# Digital_Clock.net
KiCad netlist of a schematic drawn in Altium Designer
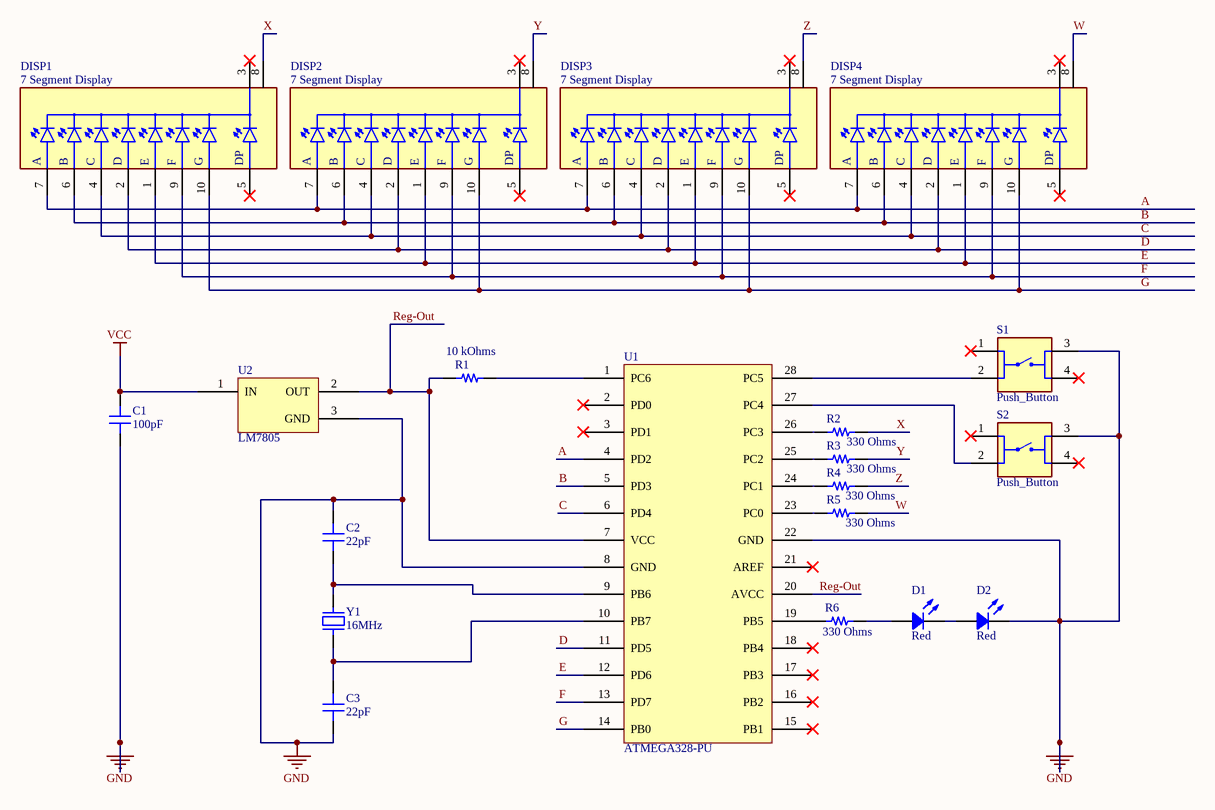
[diagram p0: Digital_Clock.SchDoc]

(export (version "E")
  (design (tool "Eeschema 10.0.6"))
  (components
    (comp (ref "C1")
      (value "100pF")
      (footprint "CAP 0805_2012")
      (description "CAP CER 100PF 25V NP0 0805")
      (fields
        (field (name "PART NUMBER") "08053A101J4T2A")
        (field (name "CAPACITANCE") "100pF")
        (field (name "MANUFACTURER") "AVX Corporation")
      )
      (libsource (lib "Celestial Altium Library - altium_library") (part "Capacitor"))
    )
    (comp (ref "C2")
      (value "22pF")
      (footprint "CAP 0805_2012")
      (description "CAP CER 22PF 50V X7R 0805")
      (fields
        (field (name "PART NUMBER") "08055C220JAT2A")
        (field (name "CAPACITANCE") "22pF")
        (field (name "MANUFACTURER") "AVX Corporation")
      )
      (libsource (lib "Celestial Altium Library - altium_library") (part "Capacitor"))
    )
    (comp (ref "C3")
      (value "22pF")
      (footprint "CAP 0805_2012")
      (description "CAP CER 22PF 50V X7R 0805")
      (fields
        (field (name "PART NUMBER") "08055C220JAT2A")
        (field (name "CAPACITANCE") "22pF")
        (field (name "MANUFACTURER") "AVX Corporation")
      )
      (libsource (lib "Celestial Altium Library - altium_library") (part "Capacitor"))
    )
    (comp (ref "D1")
      (value "Red")
      (footprint "LED 0805_2012 RED")
      (description "LED RED CLEAR 0805 SMD")
      (fields (field (name "PART NUMBER") "XZCM2CRK54WA-1VF") (field (name "MANUFACTURER") "SunLED"))
      (libsource (lib "Celestial Altium Library - altium_library") (part "LED"))
    )
    (comp (ref "D2")
      (value "Red")
      (footprint "LED 0805_2012 RED")
      (description "LED RED CLEAR 0805 SMD")
      (fields (field (name "PART NUMBER") "XZCM2CRK54WA-1VF") (field (name "MANUFACTURER") "SunLED"))
      (libsource (lib "") (part "LED_1"))
    )
    (comp (ref "DISP1")
      (value "7 Segment Display")
      (footprint "7 Segment Display")
      (libsource (lib "Digital_Clock") (part "7 Segment Display"))
    )
    (comp (ref "DISP2")
      (value "7 Segment Display")
      (footprint "7 Segment Display")
      (libsource (lib "Digital_Clock") (part "7 Segment Display"))
    )
    (comp (ref "DISP3")
      (value "7 Segment Display")
      (footprint "7 Segment Display")
      (libsource (lib "Digital_Clock") (part "7 Segment Display"))
    )
    (comp (ref "DISP4")
      (value "7 Segment Display")
      (footprint "7 Segment Display")
      (libsource (lib "Digital_Clock") (part "7 Segment Display"))
    )
    (comp (ref "R1")
      (value "10 kOhms")
      (footprint "YAGEO RES RK73 RS73 SG73 0805_2012")
      (description "RES 10K OHM 1% 1/2W 0805")
      (fields
        (field (name "PART NUMBER") "SG73P2ATTD1002F")
        (field (name "MANUFACTURER") "KOA Speer Electronics, Inc.")
      )
      (libsource (lib "Celestial Altium Library - altium_library") (part "Resistor"))
    )
    (comp (ref "R2")
      (value "330 Ohms")
      (footprint "YAGEO RES RK73 RS73 SG73 0805_2012")
      (description "RES 330 OHM 1% 1/2W 0805")
      (fields
        (field (name "PART NUMBER") "SG73P2ATTD3300F")
        (field (name "MANUFACTURER") "KOA Speer Electronics, Inc.")
      )
      (libsource (lib "Celestial Altium Library - altium_library") (part "Resistor"))
    )
    (comp (ref "R3")
      (value "330 Ohms")
      (footprint "YAGEO RES RK73 RS73 SG73 0805_2012")
      (description "RES 330 OHM 1% 1/2W 0805")
      (fields
        (field (name "PART NUMBER") "SG73P2ATTD3300F")
        (field (name "MANUFACTURER") "KOA Speer Electronics, Inc.")
      )
      (libsource (lib "Celestial Altium Library - altium_library") (part "Resistor"))
    )
    (comp (ref "R4")
      (value "330 Ohms")
      (footprint "YAGEO RES RK73 RS73 SG73 0805_2012")
      (description "RES 330 OHM 1% 1/2W 0805")
      (fields
        (field (name "PART NUMBER") "SG73P2ATTD3300F")
        (field (name "MANUFACTURER") "KOA Speer Electronics, Inc.")
      )
      (libsource (lib "Celestial Altium Library - altium_library") (part "Resistor"))
    )
    (comp (ref "R5")
      (value "330 Ohms")
      (footprint "YAGEO RES RK73 RS73 SG73 0805_2012")
      (description "RES 330 OHM 1% 1/2W 0805")
      (fields
        (field (name "PART NUMBER") "SG73P2ATTD3300F")
        (field (name "MANUFACTURER") "KOA Speer Electronics, Inc.")
      )
      (libsource (lib "Celestial Altium Library - altium_library") (part "Resistor"))
    )
    (comp (ref "R6")
      (value "330 Ohms")
      (footprint "YAGEO RES RK73 RS73 SG73 0805_2012")
      (description "RES 330 OHM 1% 1/2W 0805")
      (fields
        (field (name "PART NUMBER") "SG73P2ATTD3300F")
        (field (name "MANUFACTURER") "KOA Speer Electronics, Inc.")
      )
      (libsource (lib "Celestial Altium Library - altium_library") (part "Resistor"))
    )
    (comp (ref "S1")
      (value "Push_Button")
      (footprint "Push_Button")
      (libsource (lib "Digital_Clock") (part "Push_Button"))
    )
    (comp (ref "S2")
      (value "Push_Button")
      (footprint "Push_Button")
      (libsource (lib "Digital_Clock") (part "Push_Button"))
    )
    (comp (ref "U1")
      (value "ATMEGA328-PU")
      (footprint "ATMEGA328-PU")
      (libsource (lib "Digital_Clock") (part "ATMEGA328-PU"))
    )
    (comp (ref "U2")
      (value "LM7805")
      (footprint "LM7805CT")
      (libsource (lib "Digital_Clock") (part "LM7805"))
    )
    (comp (ref "Y1")
      (value "16MHz")
      (footprint "ABRACON ABLS")
      (description "CRYSTAL 16.0000MHZ 20PF SMD")
      (fields
        (field (name "PART NUMBER") "ABLS-16.000MHZ-20-D4H-T")
        (field (name "MANUFACTURER") "Abracon LLC")
      )
      (libsource (lib "Celestial Altium Library - altium_library") (part "Abracon Crystal ABLS"))
    )
  )
  (nets
    (net (code "1") (name "/A") (class "Default")
      (node (ref "DISP1") (pin "7") (pinfunction "A_7") (pintype "passive"))
      (node (ref "DISP2") (pin "7") (pinfunction "A_7") (pintype "passive"))
      (node (ref "DISP3") (pin "7") (pinfunction "A_7") (pintype "passive"))
      (node (ref "DISP4") (pin "7") (pinfunction "A_7") (pintype "passive"))
      (node (ref "U1") (pin "4") (pinfunction "PD2_4") (pintype "passive"))
    )
    (net (code "2") (name "/B") (class "Default")
      (node (ref "DISP1") (pin "6") (pinfunction "B_6") (pintype "passive"))
      (node (ref "DISP2") (pin "6") (pinfunction "B_6") (pintype "passive"))
      (node (ref "DISP3") (pin "6") (pinfunction "B_6") (pintype "passive"))
      (node (ref "DISP4") (pin "6") (pinfunction "B_6") (pintype "passive"))
      (node (ref "U1") (pin "5") (pinfunction "PD3_5") (pintype "passive"))
    )
    (net (code "3") (name "/C") (class "Default")
      (node (ref "DISP1") (pin "4") (pinfunction "C_4") (pintype "passive"))
      (node (ref "DISP2") (pin "4") (pinfunction "C_4") (pintype "passive"))
      (node (ref "DISP3") (pin "4") (pinfunction "C_4") (pintype "passive"))
      (node (ref "DISP4") (pin "4") (pinfunction "C_4") (pintype "passive"))
      (node (ref "U1") (pin "6") (pinfunction "PD4_6") (pintype "passive"))
    )
    (net (code "4") (name "/D") (class "Default")
      (node (ref "DISP1") (pin "2") (pinfunction "D_2") (pintype "passive"))
      (node (ref "DISP2") (pin "2") (pinfunction "D_2") (pintype "passive"))
      (node (ref "DISP3") (pin "2") (pinfunction "D_2") (pintype "passive"))
      (node (ref "DISP4") (pin "2") (pinfunction "D_2") (pintype "passive"))
      (node (ref "U1") (pin "11") (pinfunction "PD5_11") (pintype "passive"))
    )
    (net (code "5") (name "/E") (class "Default")
      (node (ref "DISP1") (pin "1") (pinfunction "E_1") (pintype "passive"))
      (node (ref "DISP2") (pin "1") (pinfunction "E_1") (pintype "passive"))
      (node (ref "DISP3") (pin "1") (pinfunction "E_1") (pintype "passive"))
      (node (ref "DISP4") (pin "1") (pinfunction "E_1") (pintype "passive"))
      (node (ref "U1") (pin "12") (pinfunction "PD6_12") (pintype "passive"))
    )
    (net (code "6") (name "/F") (class "Default")
      (node (ref "DISP1") (pin "9") (pinfunction "F_9") (pintype "passive"))
      (node (ref "DISP2") (pin "9") (pinfunction "F_9") (pintype "passive"))
      (node (ref "DISP3") (pin "9") (pinfunction "F_9") (pintype "passive"))
      (node (ref "DISP4") (pin "9") (pinfunction "F_9") (pintype "passive"))
      (node (ref "U1") (pin "13") (pinfunction "PD7_13") (pintype "passive"))
    )
    (net (code "7") (name "/G") (class "Default")
      (node (ref "DISP1") (pin "10") (pinfunction "G_10") (pintype "passive"))
      (node (ref "DISP2") (pin "10") (pinfunction "G_10") (pintype "passive"))
      (node (ref "DISP3") (pin "10") (pinfunction "G_10") (pintype "passive"))
      (node (ref "DISP4") (pin "10") (pinfunction "G_10") (pintype "passive"))
      (node (ref "U1") (pin "14") (pinfunction "PB0_14") (pintype "passive"))
    )
    (net (code "8") (name "/Reg-Out") (class "Default")
      (node (ref "R1") (pin "1") (pinfunction "1_1") (pintype "passive"))
      (node (ref "U1") (pin "20") (pinfunction "AVCC_20") (pintype "passive"))
      (node (ref "U1") (pin "7") (pinfunction "VCC_7") (pintype "passive"))
      (node (ref "U2") (pin "2") (pinfunction "OUT_2") (pintype "passive"))
    )
    (net (code "9") (name "/W") (class "Default")
      (node (ref "DISP4") (pin "8") (pinfunction "COM_8") (pintype "passive"))
      (node (ref "R5") (pin "2") (pinfunction "2_2") (pintype "passive"))
    )
    (net (code "10") (name "/X") (class "Default")
      (node (ref "DISP1") (pin "8") (pinfunction "COM_8") (pintype "passive"))
      (node (ref "R2") (pin "2") (pinfunction "2_2") (pintype "passive"))
    )
    (net (code "11") (name "/Y") (class "Default")
      (node (ref "DISP2") (pin "8") (pinfunction "COM_8") (pintype "passive"))
      (node (ref "R3") (pin "2") (pinfunction "2_2") (pintype "passive"))
    )
    (net (code "12") (name "/Z") (class "Default")
      (node (ref "DISP3") (pin "8") (pinfunction "COM_8") (pintype "passive"))
      (node (ref "R4") (pin "2") (pinfunction "2_2") (pintype "passive"))
    )
    (net (code "13") (name "GND") (class "Default")
      (node (ref "C1") (pin "1") (pinfunction "1_1") (pintype "passive"))
      (node (ref "C2") (pin "2") (pinfunction "2_2") (pintype "passive"))
      (node (ref "C3") (pin "1") (pinfunction "1_1") (pintype "passive"))
      (node (ref "D2") (pin "2") (pinfunction "2_2") (pintype "passive"))
      (node (ref "S1") (pin "3") (pinfunction "3_3") (pintype "passive"))
      (node (ref "S2") (pin "3") (pinfunction "3_3") (pintype "passive"))
      (node (ref "U1") (pin "22") (pinfunction "GND_22") (pintype "passive"))
      (node (ref "U1") (pin "8") (pinfunction "GND_8") (pintype "passive"))
      (node (ref "U2") (pin "3") (pinfunction "GND_3") (pintype "passive"))
    )
    (net (code "14") (name "Net-(D1-Pad1)") (class "Default")
      (node (ref "D1") (pin "1") (pinfunction "1_1") (pintype "passive"))
      (node (ref "D2") (pin "1") (pinfunction "1_1") (pintype "passive"))
    )
    (net (code "15") (name "Net-(D1-Pad2)") (class "Default")
      (node (ref "D1") (pin "2") (pinfunction "2_2") (pintype "passive"))
      (node (ref "R6") (pin "2") (pinfunction "2_2") (pintype "passive"))
    )
    (net (code "16") (name "Net-(U1-PB5)") (class "Default")
      (node (ref "R6") (pin "1") (pinfunction "1_1") (pintype "passive"))
      (node (ref "U1") (pin "19") (pinfunction "PB5_19") (pintype "passive"))
    )
    (net (code "17") (name "Net-(U1-PB6)") (class "Default")
      (node (ref "C2") (pin "1") (pinfunction "1_1") (pintype "passive"))
      (node (ref "U1") (pin "9") (pinfunction "PB6_9") (pintype "passive"))
      (node (ref "Y1") (pin "2") (pinfunction "2_2") (pintype "passive"))
    )
    (net (code "18") (name "Net-(U1-PB7)") (class "Default")
      (node (ref "C3") (pin "2") (pinfunction "2_2") (pintype "passive"))
      (node (ref "U1") (pin "10") (pinfunction "PB7_10") (pintype "passive"))
      (node (ref "Y1") (pin "1") (pinfunction "1_1") (pintype "passive"))
    )
    (net (code "19") (name "Net-(U1-PC0)") (class "Default")
      (node (ref "R5") (pin "1") (pinfunction "1_1") (pintype "passive"))
      (node (ref "U1") (pin "23") (pinfunction "PC0_23") (pintype "passive"))
    )
    (net (code "20") (name "Net-(U1-PC1)") (class "Default")
      (node (ref "R4") (pin "1") (pinfunction "1_1") (pintype "passive"))
      (node (ref "U1") (pin "24") (pinfunction "PC1_24") (pintype "passive"))
    )
    (net (code "21") (name "Net-(U1-PC2)") (class "Default")
      (node (ref "R3") (pin "1") (pinfunction "1_1") (pintype "passive"))
      (node (ref "U1") (pin "25") (pinfunction "PC2_25") (pintype "passive"))
    )
    (net (code "22") (name "Net-(U1-PC3)") (class "Default")
      (node (ref "R2") (pin "1") (pinfunction "1_1") (pintype "passive"))
      (node (ref "U1") (pin "26") (pinfunction "PC3_26") (pintype "passive"))
    )
    (net (code "23") (name "Net-(U1-PC4)") (class "Default")
      (node (ref "S2") (pin "2") (pinfunction "2_2") (pintype "passive"))
      (node (ref "U1") (pin "27") (pinfunction "PC4_27") (pintype "passive"))
    )
    (net (code "24") (name "Net-(U1-PC5)") (class "Default")
      (node (ref "S1") (pin "2") (pinfunction "2_2") (pintype "passive"))
      (node (ref "U1") (pin "28") (pinfunction "PC5_28") (pintype "passive"))
    )
    (net (code "25") (name "Net-(U1-PC6)") (class "Default")
      (node (ref "R1") (pin "2") (pinfunction "2_2") (pintype "passive"))
      (node (ref "U1") (pin "1") (pinfunction "PC6_1") (pintype "passive"))
    )
    (net (code "26") (name "VCC") (class "Default")
      (node (ref "C1") (pin "2") (pinfunction "2_2") (pintype "passive"))
      (node (ref "U2") (pin "1") (pinfunction "IN_1") (pintype "passive"))
    )
    (net (code "27") (name "unconnected-(DISP1-COM-Pad3)") (class "Default")
      (node (ref "DISP1") (pin "3") (pinfunction "COM_3") (pintype "passive+no_connect"))
    )
    (net (code "28") (name "unconnected-(DISP1-DP-Pad5)") (class "Default")
      (node (ref "DISP1") (pin "5") (pinfunction "DP_5") (pintype "passive+no_connect"))
    )
    (net (code "29") (name "unconnected-(DISP2-COM-Pad3)") (class "Default")
      (node (ref "DISP2") (pin "3") (pinfunction "COM_3") (pintype "passive+no_connect"))
    )
    (net (code "30") (name "unconnected-(DISP2-DP-Pad5)") (class "Default")
      (node (ref "DISP2") (pin "5") (pinfunction "DP_5") (pintype "passive+no_connect"))
    )
    (net (code "31") (name "unconnected-(DISP3-COM-Pad3)") (class "Default")
      (node (ref "DISP3") (pin "3") (pinfunction "COM_3") (pintype "passive+no_connect"))
    )
    (net (code "32") (name "unconnected-(DISP3-DP-Pad5)") (class "Default")
      (node (ref "DISP3") (pin "5") (pinfunction "DP_5") (pintype "passive+no_connect"))
    )
    (net (code "33") (name "unconnected-(DISP4-COM-Pad3)") (class "Default")
      (node (ref "DISP4") (pin "3") (pinfunction "COM_3") (pintype "passive+no_connect"))
    )
    (net (code "34") (name "unconnected-(DISP4-DP-Pad5)") (class "Default")
      (node (ref "DISP4") (pin "5") (pinfunction "DP_5") (pintype "passive+no_connect"))
    )
    (net (code "35") (name "unconnected-(S1-Pad1)") (class "Default")
      (node (ref "S1") (pin "1") (pinfunction "1_1") (pintype "passive+no_connect"))
    )
    (net (code "36") (name "unconnected-(S1-Pad4)") (class "Default")
      (node (ref "S1") (pin "4") (pinfunction "4_4") (pintype "passive+no_connect"))
    )
    (net (code "37") (name "unconnected-(S2-Pad1)") (class "Default")
      (node (ref "S2") (pin "1") (pinfunction "1_1") (pintype "passive+no_connect"))
    )
    (net (code "38") (name "unconnected-(S2-Pad4)") (class "Default")
      (node (ref "S2") (pin "4") (pinfunction "4_4") (pintype "passive+no_connect"))
    )
    (net (code "39") (name "unconnected-(U1-AREF-Pad21)") (class "Default")
      (node (ref "U1") (pin "21") (pinfunction "AREF_21") (pintype "passive+no_connect"))
    )
    (net (code "40") (name "unconnected-(U1-PB1-Pad15)") (class "Default")
      (node (ref "U1") (pin "15") (pinfunction "PB1_15") (pintype "passive+no_connect"))
    )
    (net (code "41") (name "unconnected-(U1-PB2-Pad16)") (class "Default")
      (node (ref "U1") (pin "16") (pinfunction "PB2_16") (pintype "passive+no_connect"))
    )
    (net (code "42") (name "unconnected-(U1-PB3-Pad17)") (class "Default")
      (node (ref "U1") (pin "17") (pinfunction "PB3_17") (pintype "passive+no_connect"))
    )
    (net (code "43") (name "unconnected-(U1-PB4-Pad18)") (class "Default")
      (node (ref "U1") (pin "18") (pinfunction "PB4_18") (pintype "passive+no_connect"))
    )
    (net (code "44") (name "unconnected-(U1-PD0-Pad2)") (class "Default")
      (node (ref "U1") (pin "2") (pinfunction "PD0_2") (pintype "passive+no_connect"))
    )
    (net (code "45") (name "unconnected-(U1-PD1-Pad3)") (class "Default")
      (node (ref "U1") (pin "3") (pinfunction "PD1_3") (pintype "passive+no_connect"))
    )
  )
)
